# sb-sonata-analoginput.net
KiCad netlist of a schematic drawn in Altium Designer
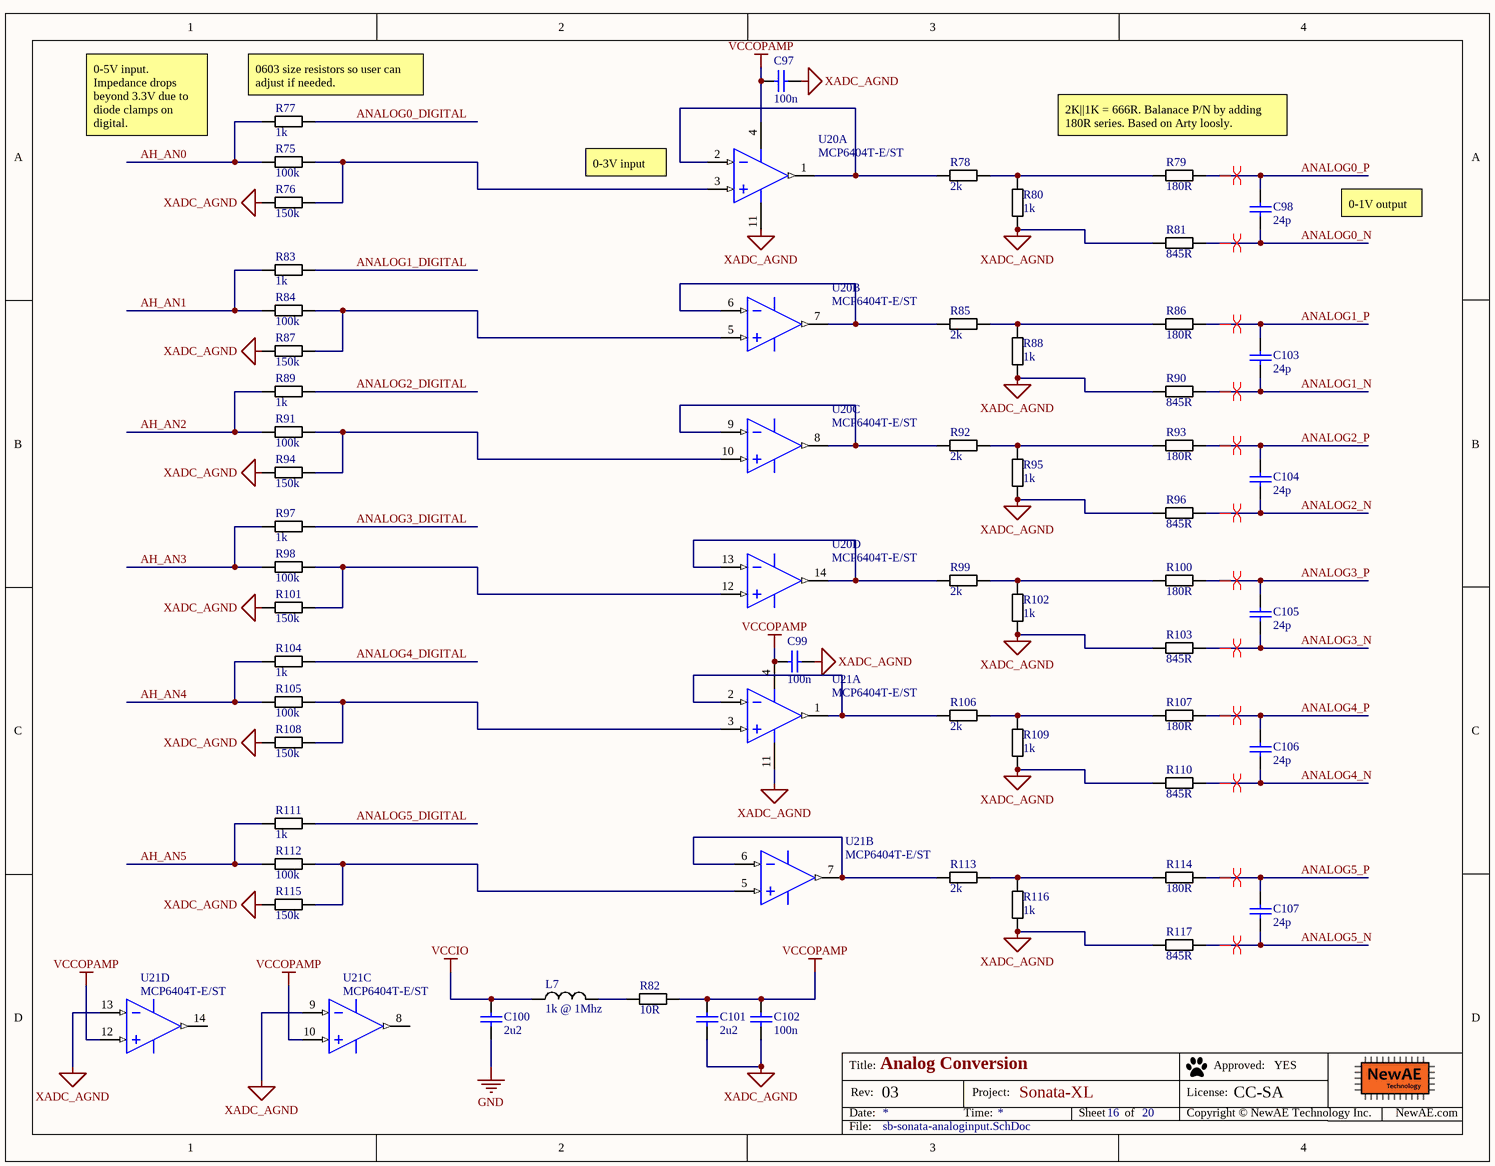
[diagram p0: sb-sonata-analoginput.SchDoc]

(export (version "E")
  (design (tool "Eeschema 10.0.6"))
  (components
    (comp (ref "C97")
      (value "100n")
      (footprint "CAPC0402_M")
      (description "100n, 0402")
      (fields (field (name "PART NUMBER") "CCHIP-100n-0402"))
      (libsource (lib "NewAE_AltiumLib") (part "CAP"))
    )
    (comp (ref "C98")
      (value "24p")
      (footprint "CAPC0402_M")
      (description "24p, 0402")
      (fields (field (name "PART NUMBER") "CCHIP-24p-0402"))
      (libsource (lib "NewAE_AltiumLib") (part "CAP"))
    )
    (comp (ref "C99")
      (value "100n")
      (footprint "CAPC0402_M")
      (description "100n, 0402")
      (fields (field (name "PART NUMBER") "CCHIP-100n-0402"))
      (libsource (lib "NewAE_AltiumLib") (part "CAP"))
    )
    (comp (ref "C100")
      (value "2u2")
      (footprint "CAPC0603_M")
      (description "2u2, 0603")
      (fields (field (name "PART NUMBER") "CCHIP-2u2-0603"))
      (libsource (lib "NewAE_AltiumLib") (part "CAP"))
    )
    (comp (ref "C101")
      (value "2u2")
      (footprint "CAPC0603_M")
      (description "2u2, 0603")
      (fields (field (name "PART NUMBER") "CCHIP-2u2-0603"))
      (libsource (lib "NewAE_AltiumLib") (part "CAP"))
    )
    (comp (ref "C102")
      (value "100n")
      (footprint "CAPC0402_M")
      (description "100n, 0402")
      (fields (field (name "PART NUMBER") "CCHIP-100n-0402"))
      (libsource (lib "NewAE_AltiumLib") (part "CAP"))
    )
    (comp (ref "C103")
      (value "24p")
      (footprint "CAPC0402_M")
      (description "24p, 0402")
      (fields (field (name "PART NUMBER") "CCHIP-24p-0402"))
      (libsource (lib "NewAE_AltiumLib") (part "CAP"))
    )
    (comp (ref "C104")
      (value "24p")
      (footprint "CAPC0402_M")
      (description "24p, 0402")
      (fields (field (name "PART NUMBER") "CCHIP-24p-0402"))
      (libsource (lib "NewAE_AltiumLib") (part "CAP"))
    )
    (comp (ref "C105")
      (value "24p")
      (footprint "CAPC0402_M")
      (description "24p, 0402")
      (fields (field (name "PART NUMBER") "CCHIP-24p-0402"))
      (libsource (lib "NewAE_AltiumLib") (part "CAP"))
    )
    (comp (ref "C106")
      (value "24p")
      (footprint "CAPC0402_M")
      (description "24p, 0402")
      (fields (field (name "PART NUMBER") "CCHIP-24p-0402"))
      (libsource (lib "NewAE_AltiumLib") (part "CAP"))
    )
    (comp (ref "C107")
      (value "24p")
      (footprint "CAPC0402_M")
      (description "24p, 0402")
      (fields (field (name "PART NUMBER") "CCHIP-24p-0402"))
      (libsource (lib "NewAE_AltiumLib") (part "CAP"))
    )
    (comp (ref "L7")
      (value "1k @ 1Mhz")
      (footprint "IND_0603")
      (description "Ferrite Beads HI CUR CHIP BD 0603 1000OHMS 25%")
      (fields (field (name "PART NUMBER") "FBCHIP-1k-0603"))
      (libsource (lib "NewAE_AltiumLib") (part "IND"))
    )
    (comp (ref "R75")
      (value "100k")
      (footprint "RESC1608X55N")
      (description "100k res, 0603, 1%, 1/10W")
      (fields (field (name "PART NUMBER") "RCHIP-100K-0603") (field (name "TOLERANCE") "1%"))
      (libsource (lib "NewAE_AltiumLib") (part "RES-EU"))
    )
    (comp (ref "R76")
      (value "150k")
      (footprint "RESC1608X55N")
      (description "150k res, 0603, 1%, 1/10W")
      (fields (field (name "PART NUMBER") "RCHIP-150K-0603") (field (name "TOLERANCE") "1%"))
      (libsource (lib "NewAE_AltiumLib") (part "RES-EU"))
    )
    (comp (ref "R77")
      (value "1k")
      (footprint "RESC1608X55N")
      (description "1k res, 0603, 1%, 1/10W")
      (fields (field (name "PART NUMBER") "RCHIP-1K-0603") (field (name "TOLERANCE") "1%"))
      (libsource (lib "NewAE_AltiumLib") (part "RES-EU"))
    )
    (comp (ref "R78")
      (value "2k")
      (footprint "RESC1005X40N")
      (description "2k res, 0402, 1%, 1/16W")
      (fields (field (name "PART NUMBER") "RCHIP-2K-0402") (field (name "TOLERANCE") "1%"))
      (libsource (lib "NewAE_AltiumLib") (part "RES-EU"))
    )
    (comp (ref "R79")
      (value "180R")
      (footprint "RESC1005X40N")
      (description "180R res, 0402, 1%, 1/16W")
      (fields (field (name "PART NUMBER") "RCHIP-180R-0402") (field (name "TOLERANCE") "1%"))
      (libsource (lib "NewAE_AltiumLib") (part "RES-EU"))
    )
    (comp (ref "R80")
      (value "1k")
      (footprint "RESC1005X40N")
      (description "1k res, 0402, 1%, 1/16W")
      (fields (field (name "PART NUMBER") "RCHIP-1K-0402") (field (name "TOLERANCE") "1%"))
      (libsource (lib "") (part "RES-EU_1"))
    )
    (comp (ref "R81")
      (value "845R")
      (footprint "RESC1005X40N")
      (description "845R res, 0402, 1%, 1/16W")
      (fields (field (name "PART NUMBER") "RCHIP-845R-0402") (field (name "TOLERANCE") "1%"))
      (libsource (lib "NewAE_AltiumLib") (part "RES-EU"))
    )
    (comp (ref "R82")
      (value "10R")
      (footprint "RESC1608X55N")
      (description "10R res, 0603, 1%, 1/10W")
      (fields (field (name "PART NUMBER") "RCHIP-10R-0603") (field (name "TOLERANCE") "1%"))
      (libsource (lib "NewAE_AltiumLib") (part "RES-EU"))
    )
    (comp (ref "R83")
      (value "1k")
      (footprint "RESC1608X55N")
      (description "1k res, 0603, 1%, 1/10W")
      (fields (field (name "PART NUMBER") "RCHIP-1K-0603") (field (name "TOLERANCE") "1%"))
      (libsource (lib "NewAE_AltiumLib") (part "RES-EU"))
    )
    (comp (ref "R84")
      (value "100k")
      (footprint "RESC1608X55N")
      (description "100k res, 0603, 1%, 1/10W")
      (fields (field (name "PART NUMBER") "RCHIP-100K-0603") (field (name "TOLERANCE") "1%"))
      (libsource (lib "NewAE_AltiumLib") (part "RES-EU"))
    )
    (comp (ref "R85")
      (value "2k")
      (footprint "RESC1005X40N")
      (description "2k res, 0402, 1%, 1/16W")
      (fields (field (name "PART NUMBER") "RCHIP-2K-0402") (field (name "TOLERANCE") "1%"))
      (libsource (lib "NewAE_AltiumLib") (part "RES-EU"))
    )
    (comp (ref "R86")
      (value "180R")
      (footprint "RESC1005X40N")
      (description "180R res, 0402, 1%, 1/16W")
      (fields (field (name "PART NUMBER") "RCHIP-180R-0402") (field (name "TOLERANCE") "1%"))
      (libsource (lib "NewAE_AltiumLib") (part "RES-EU"))
    )
    (comp (ref "R87")
      (value "150k")
      (footprint "RESC1608X55N")
      (description "150k res, 0603, 1%, 1/10W")
      (fields (field (name "PART NUMBER") "RCHIP-150K-0603") (field (name "TOLERANCE") "1%"))
      (libsource (lib "NewAE_AltiumLib") (part "RES-EU"))
    )
    (comp (ref "R88")
      (value "1k")
      (footprint "RESC1005X40N")
      (description "1k res, 0402, 1%, 1/16W")
      (fields (field (name "PART NUMBER") "RCHIP-1K-0402") (field (name "TOLERANCE") "1%"))
      (libsource (lib "") (part "RES-EU_1"))
    )
    (comp (ref "R89")
      (value "1k")
      (footprint "RESC1608X55N")
      (description "1k res, 0603, 1%, 1/10W")
      (fields (field (name "PART NUMBER") "RCHIP-1K-0603") (field (name "TOLERANCE") "1%"))
      (libsource (lib "NewAE_AltiumLib") (part "RES-EU"))
    )
    (comp (ref "R90")
      (value "845R")
      (footprint "RESC1005X40N")
      (description "845R res, 0402, 1%, 1/16W")
      (fields (field (name "PART NUMBER") "RCHIP-845R-0402") (field (name "TOLERANCE") "1%"))
      (libsource (lib "NewAE_AltiumLib") (part "RES-EU"))
    )
    (comp (ref "R91")
      (value "100k")
      (footprint "RESC1608X55N")
      (description "100k res, 0603, 1%, 1/10W")
      (fields (field (name "PART NUMBER") "RCHIP-100K-0603") (field (name "TOLERANCE") "1%"))
      (libsource (lib "NewAE_AltiumLib") (part "RES-EU"))
    )
    (comp (ref "R92")
      (value "2k")
      (footprint "RESC1005X40N")
      (description "2k res, 0402, 1%, 1/16W")
      (fields (field (name "PART NUMBER") "RCHIP-2K-0402") (field (name "TOLERANCE") "1%"))
      (libsource (lib "NewAE_AltiumLib") (part "RES-EU"))
    )
    (comp (ref "R93")
      (value "180R")
      (footprint "RESC1005X40N")
      (description "180R res, 0402, 1%, 1/16W")
      (fields (field (name "PART NUMBER") "RCHIP-180R-0402") (field (name "TOLERANCE") "1%"))
      (libsource (lib "NewAE_AltiumLib") (part "RES-EU"))
    )
    (comp (ref "R94")
      (value "150k")
      (footprint "RESC1608X55N")
      (description "150k res, 0603, 1%, 1/10W")
      (fields (field (name "PART NUMBER") "RCHIP-150K-0603") (field (name "TOLERANCE") "1%"))
      (libsource (lib "NewAE_AltiumLib") (part "RES-EU"))
    )
    (comp (ref "R95")
      (value "1k")
      (footprint "RESC1005X40N")
      (description "1k res, 0402, 1%, 1/16W")
      (fields (field (name "PART NUMBER") "RCHIP-1K-0402") (field (name "TOLERANCE") "1%"))
      (libsource (lib "") (part "RES-EU_1"))
    )
    (comp (ref "R96")
      (value "845R")
      (footprint "RESC1005X40N")
      (description "845R res, 0402, 1%, 1/16W")
      (fields (field (name "PART NUMBER") "RCHIP-845R-0402") (field (name "TOLERANCE") "1%"))
      (libsource (lib "NewAE_AltiumLib") (part "RES-EU"))
    )
    (comp (ref "R97")
      (value "1k")
      (footprint "RESC1608X55N")
      (description "1k res, 0603, 1%, 1/10W")
      (fields (field (name "PART NUMBER") "RCHIP-1K-0603") (field (name "TOLERANCE") "1%"))
      (libsource (lib "NewAE_AltiumLib") (part "RES-EU"))
    )
    (comp (ref "R98")
      (value "100k")
      (footprint "RESC1608X55N")
      (description "100k res, 0603, 1%, 1/10W")
      (fields (field (name "PART NUMBER") "RCHIP-100K-0603") (field (name "TOLERANCE") "1%"))
      (libsource (lib "NewAE_AltiumLib") (part "RES-EU"))
    )
    (comp (ref "R99")
      (value "2k")
      (footprint "RESC1005X40N")
      (description "2k res, 0402, 1%, 1/16W")
      (fields (field (name "PART NUMBER") "RCHIP-2K-0402") (field (name "TOLERANCE") "1%"))
      (libsource (lib "NewAE_AltiumLib") (part "RES-EU"))
    )
    (comp (ref "R100")
      (value "180R")
      (footprint "RESC1005X40N")
      (description "180R res, 0402, 1%, 1/16W")
      (fields (field (name "PART NUMBER") "RCHIP-180R-0402") (field (name "TOLERANCE") "1%"))
      (libsource (lib "NewAE_AltiumLib") (part "RES-EU"))
    )
    (comp (ref "R101")
      (value "150k")
      (footprint "RESC1608X55N")
      (description "150k res, 0603, 1%, 1/10W")
      (fields (field (name "PART NUMBER") "RCHIP-150K-0603") (field (name "TOLERANCE") "1%"))
      (libsource (lib "NewAE_AltiumLib") (part "RES-EU"))
    )
    (comp (ref "R102")
      (value "1k")
      (footprint "RESC1005X40N")
      (description "1k res, 0402, 1%, 1/16W")
      (fields (field (name "PART NUMBER") "RCHIP-1K-0402") (field (name "TOLERANCE") "1%"))
      (libsource (lib "") (part "RES-EU_1"))
    )
    (comp (ref "R103")
      (value "845R")
      (footprint "RESC1005X40N")
      (description "845R res, 0402, 1%, 1/16W")
      (fields (field (name "PART NUMBER") "RCHIP-845R-0402") (field (name "TOLERANCE") "1%"))
      (libsource (lib "NewAE_AltiumLib") (part "RES-EU"))
    )
    (comp (ref "R104")
      (value "1k")
      (footprint "RESC1608X55N")
      (description "1k res, 0603, 1%, 1/10W")
      (fields (field (name "PART NUMBER") "RCHIP-1K-0603") (field (name "TOLERANCE") "1%"))
      (libsource (lib "NewAE_AltiumLib") (part "RES-EU"))
    )
    (comp (ref "R105")
      (value "100k")
      (footprint "RESC1608X55N")
      (description "100k res, 0603, 1%, 1/10W")
      (fields (field (name "PART NUMBER") "RCHIP-100K-0603") (field (name "TOLERANCE") "1%"))
      (libsource (lib "NewAE_AltiumLib") (part "RES-EU"))
    )
    (comp (ref "R106")
      (value "2k")
      (footprint "RESC1005X40N")
      (description "2k res, 0402, 1%, 1/16W")
      (fields (field (name "PART NUMBER") "RCHIP-2K-0402") (field (name "TOLERANCE") "1%"))
      (libsource (lib "NewAE_AltiumLib") (part "RES-EU"))
    )
    (comp (ref "R107")
      (value "180R")
      (footprint "RESC1005X40N")
      (description "180R res, 0402, 1%, 1/16W")
      (fields (field (name "PART NUMBER") "RCHIP-180R-0402") (field (name "TOLERANCE") "1%"))
      (libsource (lib "NewAE_AltiumLib") (part "RES-EU"))
    )
    (comp (ref "R108")
      (value "150k")
      (footprint "RESC1608X55N")
      (description "150k res, 0603, 1%, 1/10W")
      (fields (field (name "PART NUMBER") "RCHIP-150K-0603") (field (name "TOLERANCE") "1%"))
      (libsource (lib "NewAE_AltiumLib") (part "RES-EU"))
    )
    (comp (ref "R109")
      (value "1k")
      (footprint "RESC1005X40N")
      (description "1k res, 0402, 1%, 1/16W")
      (fields (field (name "PART NUMBER") "RCHIP-1K-0402") (field (name "TOLERANCE") "1%"))
      (libsource (lib "") (part "RES-EU_1"))
    )
    (comp (ref "R110")
      (value "845R")
      (footprint "RESC1005X40N")
      (description "845R res, 0402, 1%, 1/16W")
      (fields (field (name "PART NUMBER") "RCHIP-845R-0402") (field (name "TOLERANCE") "1%"))
      (libsource (lib "NewAE_AltiumLib") (part "RES-EU"))
    )
    (comp (ref "R111")
      (value "1k")
      (footprint "RESC1608X55N")
      (description "1k res, 0603, 1%, 1/10W")
      (fields (field (name "PART NUMBER") "RCHIP-1K-0603") (field (name "TOLERANCE") "1%"))
      (libsource (lib "NewAE_AltiumLib") (part "RES-EU"))
    )
    (comp (ref "R112")
      (value "100k")
      (footprint "RESC1608X55N")
      (description "100k res, 0603, 1%, 1/10W")
      (fields (field (name "PART NUMBER") "RCHIP-100K-0603") (field (name "TOLERANCE") "1%"))
      (libsource (lib "NewAE_AltiumLib") (part "RES-EU"))
    )
    (comp (ref "R113")
      (value "2k")
      (footprint "RESC1005X40N")
      (description "2k res, 0402, 1%, 1/16W")
      (fields (field (name "PART NUMBER") "RCHIP-2K-0402") (field (name "TOLERANCE") "1%"))
      (libsource (lib "NewAE_AltiumLib") (part "RES-EU"))
    )
    (comp (ref "R114")
      (value "180R")
      (footprint "RESC1005X40N")
      (description "180R res, 0402, 1%, 1/16W")
      (fields (field (name "PART NUMBER") "RCHIP-180R-0402") (field (name "TOLERANCE") "1%"))
      (libsource (lib "NewAE_AltiumLib") (part "RES-EU"))
    )
    (comp (ref "R115")
      (value "150k")
      (footprint "RESC1608X55N")
      (description "150k res, 0603, 1%, 1/10W")
      (fields (field (name "PART NUMBER") "RCHIP-150K-0603") (field (name "TOLERANCE") "1%"))
      (libsource (lib "NewAE_AltiumLib") (part "RES-EU"))
    )
    (comp (ref "R116")
      (value "1k")
      (footprint "RESC1005X40N")
      (description "1k res, 0402, 1%, 1/16W")
      (fields (field (name "PART NUMBER") "RCHIP-1K-0402") (field (name "TOLERANCE") "1%"))
      (libsource (lib "") (part "RES-EU_1"))
    )
    (comp (ref "R117")
      (value "845R")
      (footprint "RESC1005X40N")
      (description "845R res, 0402, 1%, 1/16W")
      (fields (field (name "PART NUMBER") "RCHIP-845R-0402") (field (name "TOLERANCE") "1%"))
      (libsource (lib "NewAE_AltiumLib") (part "RES-EU"))
    )
    (comp (ref "U20")
      (value "MCP6404T-E/ST")
      (footprint "TSSOP-ST14_M")
      (description "None")
      (libsource (lib "Altium Content Vault") (part "AMP-OPA-MCP6404-IL14"))
    )
    (comp (ref "U21")
      (value "MCP6404T-E/ST")
      (footprint "TSSOP-ST14_M")
      (description "None")
      (libsource (lib "") (part "AMP-OPA-MCP6404-IL14_1"))
    )
  )
  (nets
    (net (code "1") (name "/AH_AN0") (class "Default")
      (node (ref "R75") (pin "1") (pinfunction "1_1") (pintype "passive"))
      (node (ref "R77") (pin "1") (pinfunction "1_1") (pintype "passive"))
    )
    (net (code "2") (name "/AH_AN1") (class "Default")
      (node (ref "R83") (pin "1") (pinfunction "1_1") (pintype "passive"))
      (node (ref "R84") (pin "1") (pinfunction "1_1") (pintype "passive"))
    )
    (net (code "3") (name "/AH_AN2") (class "Default")
      (node (ref "R89") (pin "1") (pinfunction "1_1") (pintype "passive"))
      (node (ref "R91") (pin "1") (pinfunction "1_1") (pintype "passive"))
    )
    (net (code "4") (name "/AH_AN3") (class "Default")
      (node (ref "R97") (pin "1") (pinfunction "1_1") (pintype "passive"))
      (node (ref "R98") (pin "1") (pinfunction "1_1") (pintype "passive"))
    )
    (net (code "5") (name "/AH_AN4") (class "Default")
      (node (ref "R104") (pin "1") (pinfunction "1_1") (pintype "passive"))
      (node (ref "R105") (pin "1") (pinfunction "1_1") (pintype "passive"))
    )
    (net (code "6") (name "/AH_AN5") (class "Default")
      (node (ref "R111") (pin "1") (pinfunction "1_1") (pintype "passive"))
      (node (ref "R112") (pin "1") (pinfunction "1_1") (pintype "passive"))
    )
    (net (code "7") (name "/ANALOG0_DIGITAL") (class "Default")
      (node (ref "R77") (pin "2") (pinfunction "2_2") (pintype "passive"))
    )
    (net (code "8") (name "/ANALOG0_N") (class "Default")
      (node (ref "C98") (pin "2") (pinfunction "2_2") (pintype "passive"))
      (node (ref "R81") (pin "2") (pinfunction "2_2") (pintype "passive"))
    )
    (net (code "9") (name "/ANALOG0_P") (class "Default")
      (node (ref "C98") (pin "1") (pinfunction "1_1") (pintype "passive"))
      (node (ref "R79") (pin "2") (pinfunction "2_2") (pintype "passive"))
    )
    (net (code "10") (name "/ANALOG1_DIGITAL") (class "Default")
      (node (ref "R83") (pin "2") (pinfunction "2_2") (pintype "passive"))
    )
    (net (code "11") (name "/ANALOG1_N") (class "Default")
      (node (ref "C103") (pin "2") (pinfunction "2_2") (pintype "passive"))
      (node (ref "R90") (pin "2") (pinfunction "2_2") (pintype "passive"))
    )
    (net (code "12") (name "/ANALOG1_P") (class "Default")
      (node (ref "C103") (pin "1") (pinfunction "1_1") (pintype "passive"))
      (node (ref "R86") (pin "2") (pinfunction "2_2") (pintype "passive"))
    )
    (net (code "13") (name "/ANALOG2_DIGITAL") (class "Default")
      (node (ref "R89") (pin "2") (pinfunction "2_2") (pintype "passive"))
    )
    (net (code "14") (name "/ANALOG2_N") (class "Default")
      (node (ref "C104") (pin "2") (pinfunction "2_2") (pintype "passive"))
      (node (ref "R96") (pin "2") (pinfunction "2_2") (pintype "passive"))
    )
    (net (code "15") (name "/ANALOG2_P") (class "Default")
      (node (ref "C104") (pin "1") (pinfunction "1_1") (pintype "passive"))
      (node (ref "R93") (pin "2") (pinfunction "2_2") (pintype "passive"))
    )
    (net (code "16") (name "/ANALOG3_DIGITAL") (class "Default")
      (node (ref "R97") (pin "2") (pinfunction "2_2") (pintype "passive"))
    )
    (net (code "17") (name "/ANALOG3_N") (class "Default")
      (node (ref "C105") (pin "2") (pinfunction "2_2") (pintype "passive"))
      (node (ref "R103") (pin "2") (pinfunction "2_2") (pintype "passive"))
    )
    (net (code "18") (name "/ANALOG3_P") (class "Default")
      (node (ref "C105") (pin "1") (pinfunction "1_1") (pintype "passive"))
      (node (ref "R100") (pin "2") (pinfunction "2_2") (pintype "passive"))
    )
    (net (code "19") (name "/ANALOG4_DIGITAL") (class "Default")
      (node (ref "R104") (pin "2") (pinfunction "2_2") (pintype "passive"))
    )
    (net (code "20") (name "/ANALOG4_N") (class "Default")
      (node (ref "C106") (pin "2") (pinfunction "2_2") (pintype "passive"))
      (node (ref "R110") (pin "2") (pinfunction "2_2") (pintype "passive"))
    )
    (net (code "21") (name "/ANALOG4_P") (class "Default")
      (node (ref "C106") (pin "1") (pinfunction "1_1") (pintype "passive"))
      (node (ref "R107") (pin "2") (pinfunction "2_2") (pintype "passive"))
    )
    (net (code "22") (name "/ANALOG5_DIGITAL") (class "Default")
      (node (ref "R111") (pin "2") (pinfunction "2_2") (pintype "passive"))
    )
    (net (code "23") (name "/ANALOG5_N") (class "Default")
      (node (ref "C107") (pin "2") (pinfunction "2_2") (pintype "passive"))
      (node (ref "R117") (pin "2") (pinfunction "2_2") (pintype "passive"))
    )
    (net (code "24") (name "/ANALOG5_P") (class "Default")
      (node (ref "C107") (pin "1") (pinfunction "1_1") (pintype "passive"))
      (node (ref "R114") (pin "2") (pinfunction "2_2") (pintype "passive"))
    )
    (net (code "25") (name "GND") (class "Default")
      (node (ref "C100") (pin "2") (pinfunction "2_2") (pintype "passive"))
    )
    (net (code "26") (name "Net-(L7-Pad2)") (class "Default")
      (node (ref "L7") (pin "2") (pinfunction "2_2") (pintype "passive"))
      (node (ref "R82") (pin "1") (pinfunction "1_1") (pintype "passive"))
    )
    (net (code "27") (name "Net-(R78-Pad2)") (class "Default")
      (node (ref "R78") (pin "2") (pinfunction "2_2") (pintype "passive"))
      (node (ref "R79") (pin "1") (pinfunction "1_1") (pintype "passive"))
      (node (ref "R80") (pin "1") (pinfunction "1_1") (pintype "passive"))
    )
    (net (code "28") (name "Net-(R85-Pad2)") (class "Default")
      (node (ref "R85") (pin "2") (pinfunction "2_2") (pintype "passive"))
      (node (ref "R86") (pin "1") (pinfunction "1_1") (pintype "passive"))
      (node (ref "R88") (pin "1") (pinfunction "1_1") (pintype "passive"))
    )
    (net (code "29") (name "Net-(R92-Pad2)") (class "Default")
      (node (ref "R92") (pin "2") (pinfunction "2_2") (pintype "passive"))
      (node (ref "R93") (pin "1") (pinfunction "1_1") (pintype "passive"))
      (node (ref "R95") (pin "1") (pinfunction "1_1") (pintype "passive"))
    )
    (net (code "30") (name "Net-(R100-Pad1)") (class "Default")
      (node (ref "R100") (pin "1") (pinfunction "1_1") (pintype "passive"))
      (node (ref "R102") (pin "1") (pinfunction "1_1") (pintype "passive"))
      (node (ref "R99") (pin "2") (pinfunction "2_2") (pintype "passive"))
    )
    (net (code "31") (name "Net-(R106-Pad2)") (class "Default")
      (node (ref "R106") (pin "2") (pinfunction "2_2") (pintype "passive"))
      (node (ref "R107") (pin "1") (pinfunction "1_1") (pintype "passive"))
      (node (ref "R109") (pin "1") (pinfunction "1_1") (pintype "passive"))
    )
    (net (code "32") (name "Net-(R113-Pad2)") (class "Default")
      (node (ref "R113") (pin "2") (pinfunction "2_2") (pintype "passive"))
      (node (ref "R114") (pin "1") (pinfunction "1_1") (pintype "passive"))
      (node (ref "R116") (pin "1") (pinfunction "1_1") (pintype "passive"))
    )
    (net (code "33") (name "Net-(U20A-VINA+)") (class "Default")
      (node (ref "R75") (pin "2") (pinfunction "2_2") (pintype "passive"))
      (node (ref "R76") (pin "2") (pinfunction "2_2") (pintype "passive"))
      (node (ref "U20") (pin "3") (pinfunction "VINA+_3") (pintype "input"))
    )
    (net (code "34") (name "Net-(U20A-VINA-)") (class "Default")
      (node (ref "R78") (pin "1") (pinfunction "1_1") (pintype "passive"))
      (node (ref "U20") (pin "1") (pinfunction "VOUTA_1") (pintype "output"))
      (node (ref "U20") (pin "2") (pinfunction "VINA-_2") (pintype "input"))
    )
    (net (code "35") (name "Net-(U20B-VINB+)") (class "Default")
      (node (ref "R84") (pin "2") (pinfunction "2_2") (pintype "passive"))
      (node (ref "R87") (pin "2") (pinfunction "2_2") (pintype "passive"))
      (node (ref "U20") (pin "5") (pinfunction "VINB+_5") (pintype "input"))
    )
    (net (code "36") (name "Net-(U20B-VINB-)") (class "Default")
      (node (ref "R85") (pin "1") (pinfunction "1_1") (pintype "passive"))
      (node (ref "U20") (pin "6") (pinfunction "VINB-_6") (pintype "input"))
      (node (ref "U20") (pin "7") (pinfunction "VOUTB_7") (pintype "output"))
    )
    (net (code "37") (name "Net-(U20C-VINC+)") (class "Default")
      (node (ref "R91") (pin "2") (pinfunction "2_2") (pintype "passive"))
      (node (ref "R94") (pin "2") (pinfunction "2_2") (pintype "passive"))
      (node (ref "U20") (pin "10") (pinfunction "VINC+_10") (pintype "input"))
    )
    (net (code "38") (name "Net-(U20C-VINC-)") (class "Default")
      (node (ref "R92") (pin "1") (pinfunction "1_1") (pintype "passive"))
      (node (ref "U20") (pin "8") (pinfunction "VOUTC_8") (pintype "output"))
      (node (ref "U20") (pin "9") (pinfunction "VINC-_9") (pintype "input"))
    )
    (net (code "39") (name "Net-(U20D-VIND+)") (class "Default")
      (node (ref "R101") (pin "2") (pinfunction "2_2") (pintype "passive"))
      (node (ref "R98") (pin "2") (pinfunction "2_2") (pintype "passive"))
      (node (ref "U20") (pin "12") (pinfunction "VIND+_12") (pintype "input"))
    )
    (net (code "40") (name "Net-(U20D-VIND-)") (class "Default")
      (node (ref "R99") (pin "1") (pinfunction "1_1") (pintype "passive"))
      (node (ref "U20") (pin "13") (pinfunction "VIND-_13") (pintype "input"))
      (node (ref "U20") (pin "14") (pinfunction "VOUTD_14") (pintype "output"))
    )
    (net (code "41") (name "Net-(U21A-VINA+)") (class "Default")
      (node (ref "R105") (pin "2") (pinfunction "2_2") (pintype "passive"))
      (node (ref "R108") (pin "2") (pinfunction "2_2") (pintype "passive"))
      (node (ref "U21") (pin "3") (pinfunction "VINA+_3") (pintype "input"))
    )
    (net (code "42") (name "Net-(U21A-VINA-)") (class "Default")
      (node (ref "R106") (pin "1") (pinfunction "1_1") (pintype "passive"))
      (node (ref "U21") (pin "1") (pinfunction "VOUTA_1") (pintype "output"))
      (node (ref "U21") (pin "2") (pinfunction "VINA-_2") (pintype "input"))
    )
    (net (code "43") (name "Net-(U21B-VINB+)") (class "Default")
      (node (ref "R112") (pin "2") (pinfunction "2_2") (pintype "passive"))
      (node (ref "R115") (pin "2") (pinfunction "2_2") (pintype "passive"))
      (node (ref "U21") (pin "5") (pinfunction "VINB+_5") (pintype "input"))
    )
    (net (code "44") (name "Net-(U21B-VINB-)") (class "Default")
      (node (ref "R113") (pin "1") (pinfunction "1_1") (pintype "passive"))
      (node (ref "U21") (pin "6") (pinfunction "VINB-_6") (pintype "input"))
      (node (ref "U21") (pin "7") (pinfunction "VOUTB_7") (pintype "output"))
    )
    (net (code "45") (name "VCCIO") (class "Default")
      (node (ref "C100") (pin "1") (pinfunction "1_1") (pintype "passive"))
      (node (ref "L7") (pin "1") (pinfunction "1_1") (pintype "passive"))
    )
    (net (code "46") (name "VCCOPAMP") (class "Default")
      (node (ref "C101") (pin "1") (pinfunction "1_1") (pintype "passive"))
      (node (ref "C102") (pin "1") (pinfunction "1_1") (pintype "passive"))
      (node (ref "C97") (pin "1") (pinfunction "1_1") (pintype "passive"))
      (node (ref "C99") (pin "1") (pinfunction "1_1") (pintype "passive"))
      (node (ref "R82") (pin "2") (pinfunction "2_2") (pintype "passive"))
      (node (ref "U20") (pin "4") (pinfunction "VDD_4") (pintype "power_in"))
      (node (ref "U21") (pin "10") (pinfunction "VINC+_10") (pintype "input"))
      (node (ref "U21") (pin "12") (pinfunction "VIND+_12") (pintype "input"))
      (node (ref "U21") (pin "4") (pinfunction "VDD_4") (pintype "power_in"))
    )
    (net (code "47") (name "XADC_AGND") (class "Default")
      (node (ref "C101") (pin "2") (pinfunction "2_2") (pintype "passive"))
      (node (ref "C102") (pin "2") (pinfunction "2_2") (pintype "passive"))
      (node (ref "C97") (pin "2") (pinfunction "2_2") (pintype "passive"))
      (node (ref "C99") (pin "2") (pinfunction "2_2") (pintype "passive"))
      (node (ref "R101") (pin "1") (pinfunction "1_1") (pintype "passive"))
      (node (ref "R102") (pin "2") (pinfunction "2_2") (pintype "passive"))
      (node (ref "R103") (pin "1") (pinfunction "1_1") (pintype "passive"))
      (node (ref "R108") (pin "1") (pinfunction "1_1") (pintype "passive"))
      (node (ref "R109") (pin "2") (pinfunction "2_2") (pintype "passive"))
      (node (ref "R110") (pin "1") (pinfunction "1_1") (pintype "passive"))
      (node (ref "R115") (pin "1") (pinfunction "1_1") (pintype "passive"))
      (node (ref "R116") (pin "2") (pinfunction "2_2") (pintype "passive"))
      (node (ref "R117") (pin "1") (pinfunction "1_1") (pintype "passive"))
      (node (ref "R76") (pin "1") (pinfunction "1_1") (pintype "passive"))
      (node (ref "R80") (pin "2") (pinfunction "2_2") (pintype "passive"))
      (node (ref "R81") (pin "1") (pinfunction "1_1") (pintype "passive"))
      (node (ref "R87") (pin "1") (pinfunction "1_1") (pintype "passive"))
      (node (ref "R88") (pin "2") (pinfunction "2_2") (pintype "passive"))
      (node (ref "R90") (pin "1") (pinfunction "1_1") (pintype "passive"))
      (node (ref "R94") (pin "1") (pinfunction "1_1") (pintype "passive"))
      (node (ref "R95") (pin "2") (pinfunction "2_2") (pintype "passive"))
      (node (ref "R96") (pin "1") (pinfunction "1_1") (pintype "passive"))
      (node (ref "U20") (pin "11") (pinfunction "VSS_11") (pintype "power_in"))
      (node (ref "U21") (pin "11") (pinfunction "VSS_11") (pintype "power_in"))
      (node (ref "U21") (pin "13") (pinfunction "VIND-_13") (pintype "input"))
      (node (ref "U21") (pin "9") (pinfunction "VINC-_9") (pintype "input"))
    )
    (net (code "48") (name "unconnected-(U21C-VOUTC-Pad8)") (class "Default")
      (node (ref "U21") (pin "8") (pinfunction "VOUTC_8") (pintype "output"))
    )
    (net (code "49") (name "unconnected-(U21D-VOUTD-Pad14)") (class "Default")
      (node (ref "U21") (pin "14") (pinfunction "VOUTD_14") (pintype "output"))
    )
  )
)
